# Sheet2.net
KiCad netlist of a schematic drawn in Altium Designer
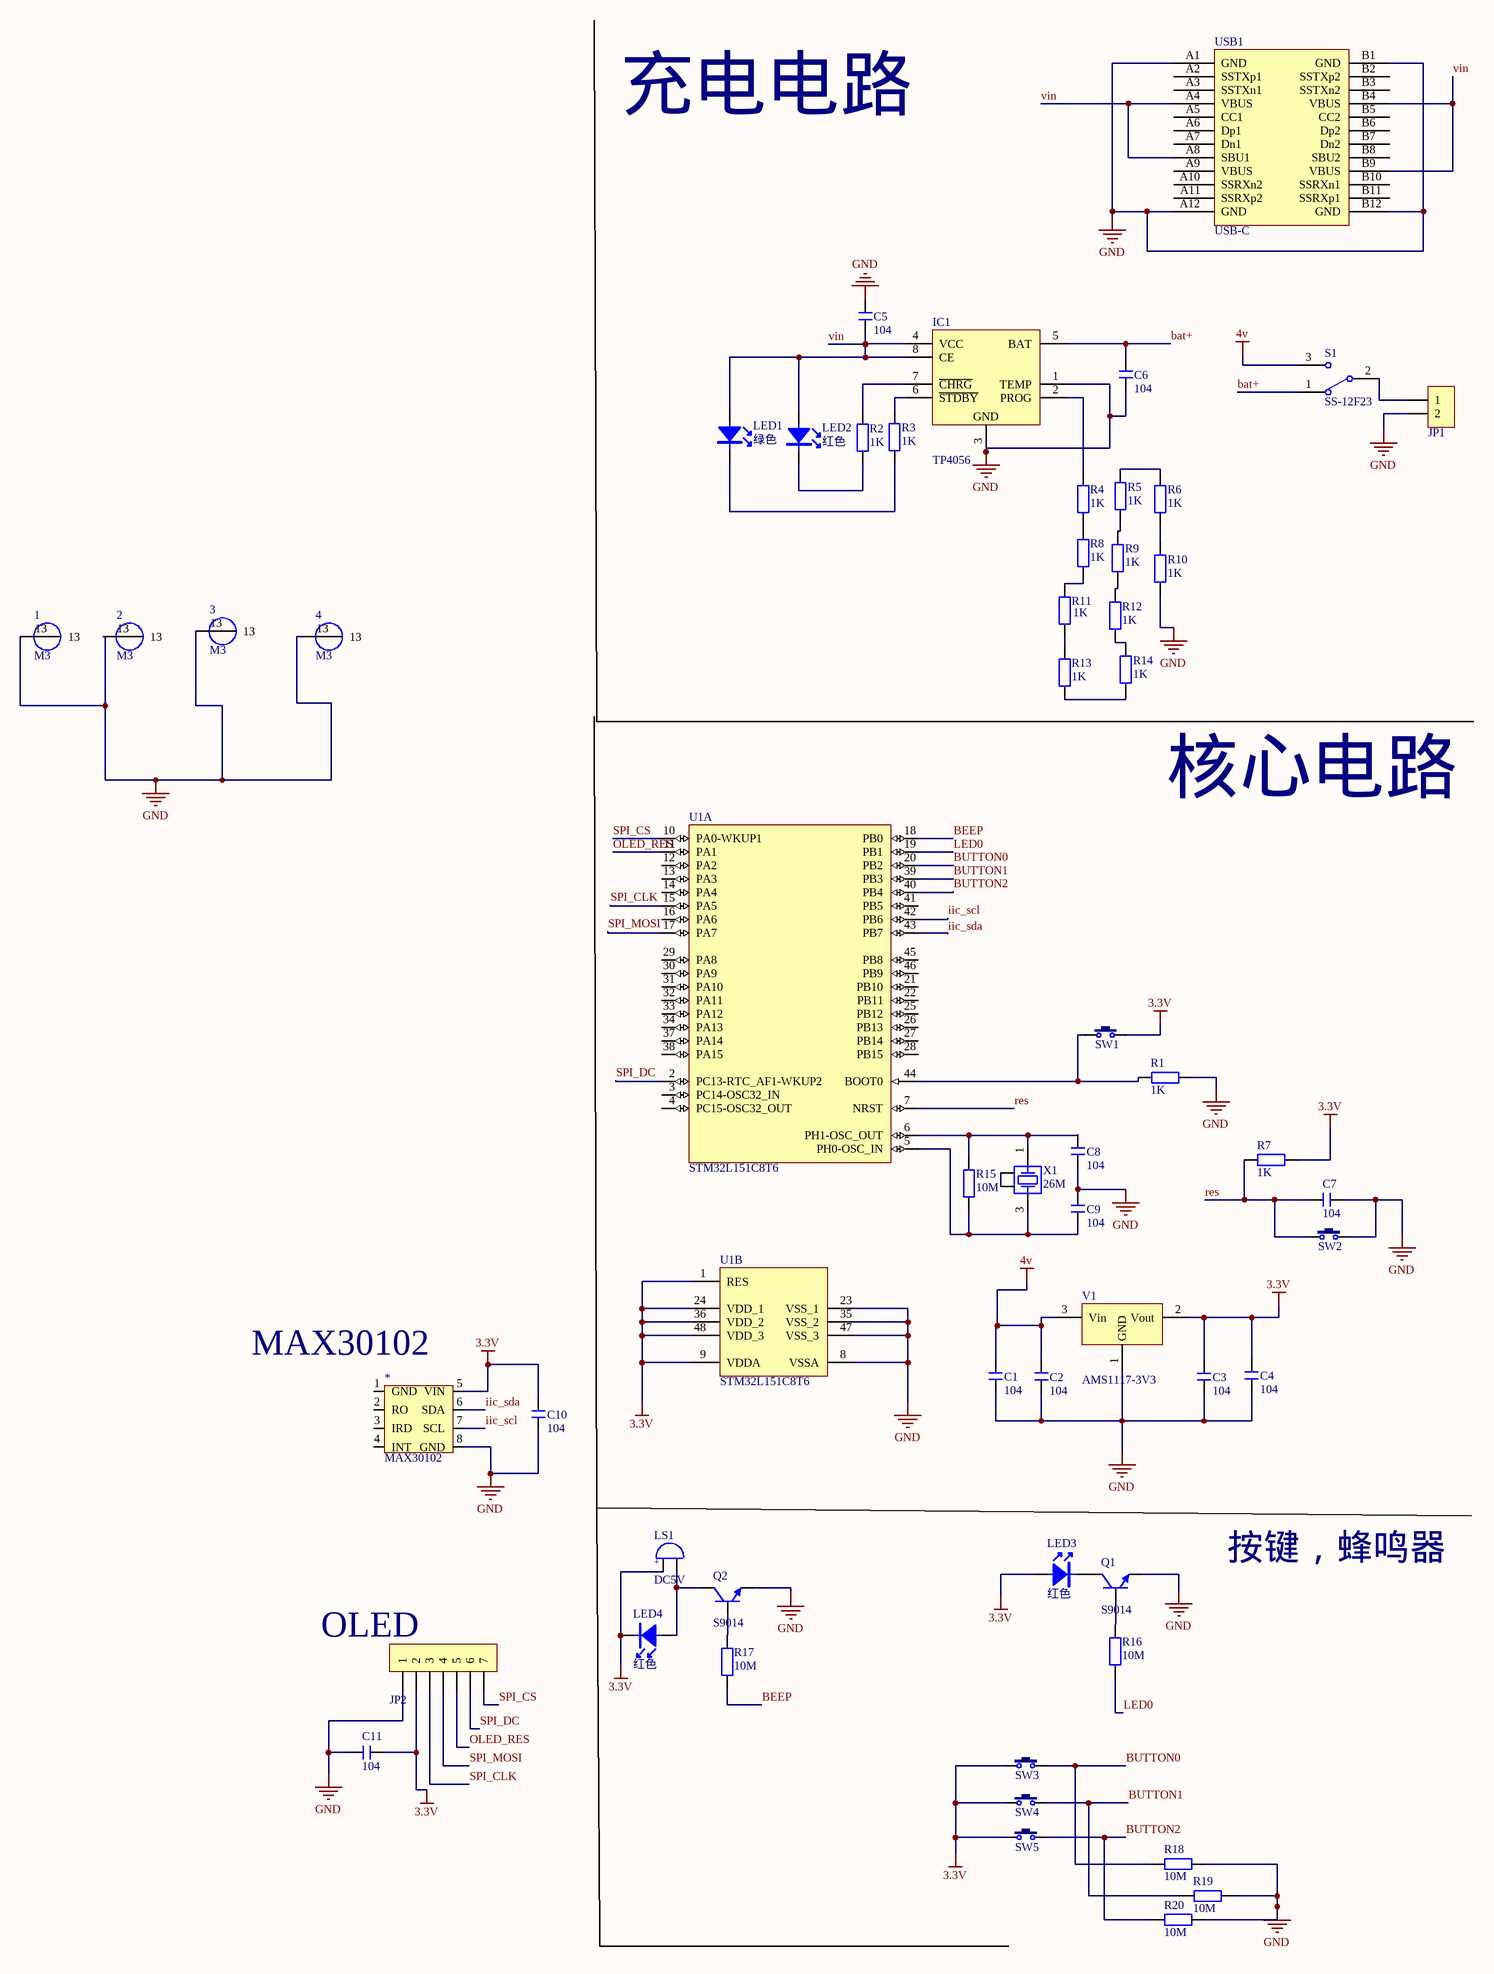
[diagram p0: Sheet2.SchDoc]

(export (version "E")
  (design (tool "Eeschema 10.0.6"))
  (components
    (comp (ref "*") (value "MAX30102") (footprint "MAX30102") (libsource (lib "Schlib1") (part "MAX30102")))
    (comp (ref "1")
      (value "M3")
      (footprint "M3 125X200")
      (description "铜柱孔")
      (libsource (lib "10 - 未分类元器件") (part "M3"))
    )
    (comp (ref "2")
      (value "M3")
      (footprint "M3 125X200")
      (description "铜柱孔")
      (libsource (lib "10 - 未分类元器件") (part "M3"))
    )
    (comp (ref "3")
      (value "M3")
      (footprint "M3 125X200")
      (description "铜柱孔")
      (libsource (lib "10 - 未分类元器件") (part "M3"))
    )
    (comp (ref "4")
      (value "M3")
      (footprint "M3 125X200")
      (description "铜柱孔")
      (libsource (lib "10 - 未分类元器件") (part "M3"))
    )
    (comp (ref "C1")
      (value "104")
      (footprint "C 0805_L")
      (description "贴片电容")
      (libsource (lib "01 - 电容-电阻-电感") (part "C"))
    )
    (comp (ref "C2")
      (value "104")
      (footprint "C 0805_L")
      (description "贴片电容")
      (libsource (lib "01 - 电容-电阻-电感") (part "C"))
    )
    (comp (ref "C3")
      (value "104")
      (footprint "C 0805_L")
      (description "贴片电容")
      (libsource (lib "01 - 电容-电阻-电感") (part "C"))
    )
    (comp (ref "C4")
      (value "104")
      (footprint "C 0805_L")
      (description "贴片电容")
      (libsource (lib "01 - 电容-电阻-电感") (part "C"))
    )
    (comp (ref "C5")
      (value "104")
      (footprint "C 0805_L")
      (description "贴片电容")
      (libsource (lib "01 - 电容-电阻-电感") (part "C"))
    )
    (comp (ref "C6")
      (value "104")
      (footprint "C 0805_L")
      (description "贴片电容")
      (libsource (lib "01 - 电容-电阻-电感") (part "C"))
    )
    (comp (ref "C7")
      (value "104")
      (footprint "C 0805_L")
      (description "贴片电容")
      (libsource (lib "01 - 电容-电阻-电感") (part "C"))
    )
    (comp (ref "C8")
      (value "104")
      (footprint "C 0805_L")
      (description "贴片电容")
      (libsource (lib "01 - 电容-电阻-电感") (part "C"))
    )
    (comp (ref "C9")
      (value "104")
      (footprint "C 0805_L")
      (description "贴片电容")
      (libsource (lib "01 - 电容-电阻-电感") (part "C"))
    )
    (comp (ref "C10")
      (value "104")
      (footprint "C 0805_L")
      (description "贴片电容")
      (libsource (lib "01 - 电容-电阻-电感") (part "C"))
    )
    (comp (ref "C11")
      (value "104")
      (footprint "C 0805_L")
      (description "贴片电容")
      (libsource (lib "01 - 电容-电阻-电感") (part "C"))
    )
    (comp (ref "IC1")
      (value "TP4056")
      (footprint "SOP8_N")
      (description "锂电池充电管理")
      (libsource (lib "08 - 稳压芯片-电源管理芯片") (part "TP4056"))
    )
    (comp (ref "JP1")
      (value "HDR-1X2")
      (footprint "HDR2.54-LI-2P")
      (description "2P接插件")
      (libsource (lib "16 - 接插件-脚距2.54mm (100mil) ") (part "Header 2"))
    )
    (comp (ref "JP2")
      (value "HDR-1X7")
      (footprint "HDR2.54-LI-7P")
      (description "7P接插件")
      (libsource (lib "16 - 接插件-脚距2.54mm (100mil) ") (part "Header 7"))
    )
    (comp (ref "LED1")
      (value "绿色")
      (footprint "LED 0805G")
      (description "贴片LED")
      (libsource (lib "02 - 二极管(LED)-三极管-整流桥") (part "LED-SMD"))
    )
    (comp (ref "LED2")
      (value "红色")
      (footprint "LED 0805G")
      (description "贴片LED")
      (libsource (lib "02 - 二极管(LED)-三极管-整流桥") (part "LED-SMD"))
    )
    (comp (ref "LED3")
      (value "红色")
      (footprint "LED 0805G")
      (description "贴片LED")
      (libsource (lib "02 - 二极管(LED)-三极管-整流桥") (part "LED-SMD"))
    )
    (comp (ref "LED4")
      (value "红色")
      (footprint "LED 0805G")
      (description "贴片LED")
      (libsource (lib "02 - 二极管(LED)-三极管-整流桥") (part "LED-SMD"))
    )
    (comp (ref "LS1")
      (value "DC5V")
      (footprint "BEEP 5x9x5.5")
      (description "有源蜂鸣器")
      (libsource (lib "03 - 按键-开关-晶振-蜂鸣器") (part "BEEP"))
    )
    (comp (ref "Q1")
      (value "S9014")
      (footprint "SOT23-3N")
      (description "低噪放大-NPN型")
      (libsource (lib "02 - 二极管(LED)-三极管-整流桥") (part "9014-SMD"))
    )
    (comp (ref "Q2")
      (value "S9014")
      (footprint "SOT23-3N")
      (description "低噪放大-NPN型")
      (libsource (lib "02 - 二极管(LED)-三极管-整流桥") (part "9014-SMD"))
    )
    (comp (ref "R1")
      (value "1K")
      (footprint "R 0805_L")
      (description "贴片电阻")
      (libsource (lib "01 - 电容-电阻-电感") (part "R"))
    )
    (comp (ref "R2")
      (value "1K")
      (footprint "R 0805_L")
      (description "贴片电阻")
      (libsource (lib "01 - 电容-电阻-电感") (part "R"))
    )
    (comp (ref "R3")
      (value "1K")
      (footprint "R 0805_L")
      (description "贴片电阻")
      (libsource (lib "01 - 电容-电阻-电感") (part "R"))
    )
    (comp (ref "R4")
      (value "1K")
      (footprint "R 0805_L")
      (description "贴片电阻")
      (libsource (lib "01 - 电容-电阻-电感") (part "R"))
    )
    (comp (ref "R5")
      (value "1K")
      (footprint "R 0805_L")
      (description "贴片电阻")
      (libsource (lib "01 - 电容-电阻-电感") (part "R"))
    )
    (comp (ref "R6")
      (value "1K")
      (footprint "R 0805_L")
      (description "贴片电阻")
      (libsource (lib "01 - 电容-电阻-电感") (part "R"))
    )
    (comp (ref "R7")
      (value "1K")
      (footprint "R 0805_L")
      (description "贴片电阻")
      (libsource (lib "01 - 电容-电阻-电感") (part "R"))
    )
    (comp (ref "R8")
      (value "1K")
      (footprint "R 0805_L")
      (description "贴片电阻")
      (libsource (lib "01 - 电容-电阻-电感") (part "R"))
    )
    (comp (ref "R9")
      (value "1K")
      (footprint "R 0805_L")
      (description "贴片电阻")
      (libsource (lib "01 - 电容-电阻-电感") (part "R"))
    )
    (comp (ref "R10")
      (value "1K")
      (footprint "R 0805_L")
      (description "贴片电阻")
      (libsource (lib "01 - 电容-电阻-电感") (part "R"))
    )
    (comp (ref "R11")
      (value "1K")
      (footprint "R 0805_L")
      (description "贴片电阻")
      (libsource (lib "01 - 电容-电阻-电感") (part "R"))
    )
    (comp (ref "R12")
      (value "1K")
      (footprint "R 0805_L")
      (description "贴片电阻")
      (libsource (lib "01 - 电容-电阻-电感") (part "R"))
    )
    (comp (ref "R13")
      (value "1K")
      (footprint "R 0805_L")
      (description "贴片电阻")
      (libsource (lib "01 - 电容-电阻-电感") (part "R"))
    )
    (comp (ref "R14")
      (value "1K")
      (footprint "R 0805_L")
      (description "贴片电阻")
      (libsource (lib "01 - 电容-电阻-电感") (part "R"))
    )
    (comp (ref "R15")
      (value "10M")
      (footprint "R 0805_L")
      (description "贴片电阻")
      (libsource (lib "01 - 电容-电阻-电感") (part "R"))
    )
    (comp (ref "R16")
      (value "10M")
      (footprint "R 0805_L")
      (description "贴片电阻")
      (libsource (lib "01 - 电容-电阻-电感") (part "R"))
    )
    (comp (ref "R17")
      (value "10M")
      (footprint "R 0805_L")
      (description "贴片电阻")
      (libsource (lib "01 - 电容-电阻-电感") (part "R"))
    )
    (comp (ref "R18")
      (value "10M")
      (footprint "R 0805_L")
      (description "贴片电阻")
      (libsource (lib "01 - 电容-电阻-电感") (part "R"))
    )
    (comp (ref "R19")
      (value "10M")
      (footprint "R 0805_L")
      (description "贴片电阻")
      (libsource (lib "01 - 电容-电阻-电感") (part "R"))
    )
    (comp (ref "R20")
      (value "10M")
      (footprint "R 0805_L")
      (description "贴片电阻")
      (libsource (lib "01 - 电容-电阻-电感") (part "R"))
    )
    (comp (ref "S1")
      (value "SS-12F23")
      (footprint "SS-12F23")
      (description "1路波动开关")
      (libsource (lib "03 - 按键-开关-晶振-蜂鸣器") (part "SSW-1P"))
    )
    (comp (ref "SW1")
      (value "3x6x5")
      (footprint "TSW SMD-3*6*2.5")
      (description "3x6轻触开关")
      (libsource (lib "03 - 按键-开关-晶振-蜂鸣器") (part "TSW 3x6"))
    )
    (comp (ref "SW2")
      (value "3x6x5")
      (footprint "TSW SMD-3*6*2.5")
      (description "3x6轻触开关")
      (libsource (lib "03 - 按键-开关-晶振-蜂鸣器") (part "TSW 3x6"))
    )
    (comp (ref "SW3")
      (value "3x6x5")
      (footprint "TSW SMD-3*6*2.5")
      (description "3x6轻触开关")
      (libsource (lib "03 - 按键-开关-晶振-蜂鸣器") (part "TSW 3x6"))
    )
    (comp (ref "SW4")
      (value "3x6x5")
      (footprint "TSW SMD-3*6*2.5")
      (description "3x6轻触开关")
      (libsource (lib "03 - 按键-开关-晶振-蜂鸣器") (part "TSW 3x6"))
    )
    (comp (ref "SW5")
      (value "3x6x5")
      (footprint "TSW SMD-3*6*2.5")
      (description "3x6轻触开关")
      (libsource (lib "03 - 按键-开关-晶振-蜂鸣器") (part "TSW 3x6"))
    )
    (comp (ref "U1")
      (value "STM32L151C8T6")
      (footprint "LQFP48_N")
      (libsource (lib "28 - STM32 L1系列单片机") (part "STM32L151C8T6"))
    )
    (comp (ref "USB1")
      (value "USB-C")
      (footprint "USB-C/S_A")
      (description "USB-C型母接口")
      (libsource (lib "04 - USB接口-网口-接口类") (part "USB-C/S"))
    )
    (comp (ref "V1")
      (value "AMS1117-3V3")
      (footprint "SOT223_L")
      (description "三端稳压芯片")
      (libsource (lib "08 - 稳压芯片-电源管理芯片") (part "AMS1117"))
    )
    (comp (ref "X1")
      (value "26M")
      (footprint "OSC 1612-4P")
      (description "4脚无源晶振")
      (libsource (lib "03 - 按键-开关-晶振-蜂鸣器") (part "XTAL-4P"))
    )
  )
  (nets
    (net (code "1") (name "/BEEP") (class "Default")
      (node (ref "R17") (pin "2") (pinfunction "2_2") (pintype "passive"))
      (node (ref "U1") (pin "18") (pinfunction "PB0_18") (pintype "bidirectional"))
    )
    (net (code "2") (name "/BUTTON0") (class "Default")
      (node (ref "R18") (pin "1") (pinfunction "1_1") (pintype "passive"))
      (node (ref "SW3") (pin "2") (pinfunction "2_2") (pintype "passive"))
      (node (ref "U1") (pin "20") (pinfunction "PB2_20") (pintype "bidirectional"))
    )
    (net (code "3") (name "/BUTTON1") (class "Default")
      (node (ref "R19") (pin "1") (pinfunction "1_1") (pintype "passive"))
      (node (ref "SW4") (pin "2") (pinfunction "2_2") (pintype "passive"))
      (node (ref "U1") (pin "39") (pinfunction "PB3_39") (pintype "bidirectional"))
    )
    (net (code "4") (name "/BUTTON2") (class "Default")
      (node (ref "R20") (pin "1") (pinfunction "1_1") (pintype "passive"))
      (node (ref "SW5") (pin "2") (pinfunction "2_2") (pintype "passive"))
      (node (ref "U1") (pin "40") (pinfunction "PB4_40") (pintype "bidirectional"))
    )
    (net (code "5") (name "/LED0") (class "Default")
      (node (ref "R16") (pin "2") (pinfunction "2_2") (pintype "passive"))
      (node (ref "U1") (pin "19") (pinfunction "PB1_19") (pintype "bidirectional"))
    )
    (net (code "6") (name "/OLED_RES") (class "Default")
      (node (ref "JP2") (pin "5") (pinfunction "5_5") (pintype "passive"))
      (node (ref "U1") (pin "11") (pinfunction "PA1_11") (pintype "bidirectional"))
    )
    (net (code "7") (name "/SPI_CLK") (class "Default")
      (node (ref "JP2") (pin "3") (pinfunction "3_3") (pintype "passive"))
      (node (ref "U1") (pin "15") (pinfunction "PA5_15") (pintype "bidirectional"))
    )
    (net (code "8") (name "/SPI_CS") (class "Default")
      (node (ref "JP2") (pin "7") (pinfunction "7_7") (pintype "passive"))
      (node (ref "U1") (pin "10") (pinfunction "PA0-WKUP1_10") (pintype "bidirectional"))
    )
    (net (code "9") (name "/SPI_DC") (class "Default")
      (node (ref "JP2") (pin "6") (pinfunction "6_6") (pintype "passive"))
      (node (ref "U1") (pin "2") (pinfunction "PC13-RTC_AF1-WKUP2_2") (pintype "bidirectional"))
    )
    (net (code "10") (name "/SPI_MOSI") (class "Default")
      (node (ref "JP2") (pin "4") (pinfunction "4_4") (pintype "passive"))
      (node (ref "U1") (pin "17") (pinfunction "PA7_17") (pintype "bidirectional"))
    )
    (net (code "11") (name "/bat+") (class "Default")
      (node (ref "C6") (pin "2") (pinfunction "2_2") (pintype "passive"))
      (node (ref "IC1") (pin "5") (pinfunction "BAT_5") (pintype "passive"))
      (node (ref "S1") (pin "1") (pinfunction "1_1") (pintype "passive"))
    )
    (net (code "12") (name "/iic_scl") (class "Default")
      (node (ref "*") (pin "7") (pinfunction "SCL_7") (pintype "passive"))
      (node (ref "U1") (pin "42") (pinfunction "PB6_42") (pintype "bidirectional"))
    )
    (net (code "13") (name "/iic_sda") (class "Default")
      (node (ref "*") (pin "6") (pinfunction "SDA_6") (pintype "passive"))
      (node (ref "U1") (pin "43") (pinfunction "PB7_43") (pintype "bidirectional"))
    )
    (net (code "14") (name "/res") (class "Default")
      (node (ref "C7") (pin "1") (pinfunction "1_1") (pintype "passive"))
      (node (ref "R7") (pin "2") (pinfunction "2_2") (pintype "passive"))
      (node (ref "SW2") (pin "1") (pinfunction "1_1") (pintype "passive"))
      (node (ref "U1") (pin "7") (pinfunction "NRST_7") (pintype "bidirectional"))
    )
    (net (code "15") (name "/vin") (class "Default")
      (node (ref "C5") (pin "1") (pinfunction "1_1") (pintype "passive"))
      (node (ref "IC1") (pin "4") (pinfunction "VCC_4") (pintype "passive"))
      (node (ref "IC1") (pin "8") (pinfunction "CE_8") (pintype "passive"))
      (node (ref "LED1") (pin "1") (pinfunction "A_1") (pintype "passive"))
      (node (ref "LED2") (pin "1") (pinfunction "A_1") (pintype "passive"))
      (node (ref "USB1") (pin "A4") (pinfunction "VBUS_A4") (pintype "passive"))
      (node (ref "USB1") (pin "A8") (pinfunction "SBU1_A8") (pintype "passive"))
      (node (ref "USB1") (pin "B4") (pinfunction "VBUS_B4") (pintype "passive"))
      (node (ref "USB1") (pin "B9") (pinfunction "VBUS_B9") (pintype "passive"))
    )
    (net (code "16") (name "3.3V") (class "Default")
      (node (ref "*") (pin "5") (pinfunction "VIN_5") (pintype "passive"))
      (node (ref "C10") (pin "1") (pinfunction "1_1") (pintype "passive"))
      (node (ref "C11") (pin "1") (pinfunction "1_1") (pintype "passive"))
      (node (ref "C3") (pin "1") (pinfunction "1_1") (pintype "passive"))
      (node (ref "C4") (pin "1") (pinfunction "1_1") (pintype "passive"))
      (node (ref "JP2") (pin "2") (pinfunction "2_2") (pintype "passive"))
      (node (ref "LED3") (pin "1") (pinfunction "A_1") (pintype "passive"))
      (node (ref "LED4") (pin "2") (pinfunction "K_2") (pintype "passive"))
      (node (ref "LS1") (pin "1") (pinfunction "1_1") (pintype "passive"))
      (node (ref "R7") (pin "1") (pinfunction "1_1") (pintype "passive"))
      (node (ref "SW1") (pin "2") (pinfunction "2_2") (pintype "passive"))
      (node (ref "SW3") (pin "1") (pinfunction "1_1") (pintype "passive"))
      (node (ref "SW4") (pin "1") (pinfunction "1_1") (pintype "passive"))
      (node (ref "SW5") (pin "1") (pinfunction "1_1") (pintype "passive"))
      (node (ref "U1") (pin "1") (pinfunction "RES_1") (pintype "power_in"))
      (node (ref "U1") (pin "24") (pinfunction "VDD_1_24") (pintype "power_in"))
      (node (ref "U1") (pin "36") (pinfunction "VDD_2_36") (pintype "power_in"))
      (node (ref "U1") (pin "48") (pinfunction "VDD_3_48") (pintype "power_in"))
      (node (ref "U1") (pin "9") (pinfunction "VDDA_9") (pintype "power_in"))
      (node (ref "V1") (pin "2") (pinfunction "Vout_2") (pintype "passive"))
    )
    (net (code "17") (name "4v") (class "Default")
      (node (ref "C1") (pin "1") (pinfunction "1_1") (pintype "passive"))
      (node (ref "C2") (pin "1") (pinfunction "1_1") (pintype "passive"))
      (node (ref "S1") (pin "3") (pinfunction "3_3") (pintype "passive"))
      (node (ref "V1") (pin "3") (pinfunction "Vin_3") (pintype "passive"))
    )
    (net (code "18") (name "GND") (class "Default")
      (node (ref "*") (pin "8") (pinfunction "GND_8") (pintype "passive"))
      (node (ref "1") (pin "13") (pinfunction "13_13") (pintype "passive"))
      (node (ref "2") (pin "13") (pinfunction "13_13") (pintype "passive"))
      (node (ref "3") (pin "13") (pinfunction "13_13") (pintype "passive"))
      (node (ref "4") (pin "13") (pinfunction "13_13") (pintype "passive"))
      (node (ref "C1") (pin "2") (pinfunction "2_2") (pintype "passive"))
      (node (ref "C10") (pin "2") (pinfunction "2_2") (pintype "passive"))
      (node (ref "C11") (pin "2") (pinfunction "2_2") (pintype "passive"))
      (node (ref "C2") (pin "2") (pinfunction "2_2") (pintype "passive"))
      (node (ref "C3") (pin "2") (pinfunction "2_2") (pintype "passive"))
      (node (ref "C4") (pin "2") (pinfunction "2_2") (pintype "passive"))
      (node (ref "C5") (pin "2") (pinfunction "2_2") (pintype "passive"))
      (node (ref "C6") (pin "1") (pinfunction "1_1") (pintype "passive"))
      (node (ref "C7") (pin "2") (pinfunction "2_2") (pintype "passive"))
      (node (ref "C8") (pin "2") (pinfunction "2_2") (pintype "passive"))
      (node (ref "C9") (pin "1") (pinfunction "1_1") (pintype "passive"))
      (node (ref "IC1") (pin "1") (pinfunction "TEMP_1") (pintype "passive"))
      (node (ref "IC1") (pin "3") (pinfunction "GND_3") (pintype "passive"))
      (node (ref "JP1") (pin "2") (pinfunction "2_2") (pintype "passive"))
      (node (ref "JP2") (pin "1") (pinfunction "1_1") (pintype "passive"))
      (node (ref "Q1") (pin "2") (pinfunction "E_2") (pintype "passive"))
      (node (ref "Q2") (pin "2") (pinfunction "E_2") (pintype "passive"))
      (node (ref "R1") (pin "1") (pinfunction "1_1") (pintype "passive"))
      (node (ref "R10") (pin "2") (pinfunction "2_2") (pintype "passive"))
      (node (ref "R18") (pin "2") (pinfunction "2_2") (pintype "passive"))
      (node (ref "R19") (pin "2") (pinfunction "2_2") (pintype "passive"))
      (node (ref "R20") (pin "2") (pinfunction "2_2") (pintype "passive"))
      (node (ref "SW2") (pin "2") (pinfunction "2_2") (pintype "passive"))
      (node (ref "U1") (pin "23") (pinfunction "VSS_1_23") (pintype "power_in"))
      (node (ref "U1") (pin "35") (pinfunction "VSS_2_35") (pintype "power_in"))
      (node (ref "U1") (pin "47") (pinfunction "VSS_3_47") (pintype "power_in"))
      (node (ref "U1") (pin "8") (pinfunction "VSSA_8") (pintype "power_in"))
      (node (ref "USB1") (pin "A1") (pinfunction "GND_A1") (pintype "passive"))
      (node (ref "USB1") (pin "A12") (pinfunction "GND_A12") (pintype "passive"))
      (node (ref "USB1") (pin "B1") (pinfunction "GND_B1") (pintype "passive"))
      (node (ref "USB1") (pin "B12") (pinfunction "GND_B12") (pintype "passive"))
      (node (ref "V1") (pin "1") (pinfunction "GND_1") (pintype "passive"))
    )
    (net (code "19") (name "Net-(IC1-PROG)") (class "Default")
      (node (ref "IC1") (pin "2") (pinfunction "PROG_2") (pintype "passive"))
      (node (ref "R4") (pin "1") (pinfunction "1_1") (pintype "passive"))
    )
    (net (code "20") (name "Net-(IC1-~{CHRG})") (class "Default")
      (node (ref "IC1") (pin "7") (pinfunction "~{CHRG}_7") (pintype "passive"))
      (node (ref "R2") (pin "1") (pinfunction "1_1") (pintype "passive"))
    )
    (net (code "21") (name "Net-(IC1-~{STDBY})") (class "Default")
      (node (ref "IC1") (pin "6") (pinfunction "~{STDBY}_6") (pintype "passive"))
      (node (ref "R3") (pin "1") (pinfunction "1_1") (pintype "passive"))
    )
    (net (code "22") (name "Net-(JP1-Pad1)") (class "Default")
      (node (ref "JP1") (pin "1") (pinfunction "1_1") (pintype "passive"))
      (node (ref "S1") (pin "2") (pinfunction "2_2") (pintype "passive"))
    )
    (net (code "23") (name "Net-(LED1-K)") (class "Default")
      (node (ref "LED1") (pin "2") (pinfunction "K_2") (pintype "passive"))
      (node (ref "R3") (pin "2") (pinfunction "2_2") (pintype "passive"))
    )
    (net (code "24") (name "Net-(LED2-K)") (class "Default")
      (node (ref "LED2") (pin "2") (pinfunction "K_2") (pintype "passive"))
      (node (ref "R2") (pin "2") (pinfunction "2_2") (pintype "passive"))
    )
    (net (code "25") (name "Net-(LED3-K)") (class "Default")
      (node (ref "LED3") (pin "2") (pinfunction "K_2") (pintype "passive"))
      (node (ref "Q1") (pin "3") (pinfunction "C_3") (pintype "passive"))
    )
    (net (code "26") (name "Net-(LED4-A)") (class "Default")
      (node (ref "LED4") (pin "1") (pinfunction "A_1") (pintype "passive"))
      (node (ref "LS1") (pin "2") (pinfunction "2_2") (pintype "passive"))
      (node (ref "Q2") (pin "3") (pinfunction "C_3") (pintype "passive"))
    )
    (net (code "27") (name "Net-(Q1-B)") (class "Default")
      (node (ref "Q1") (pin "1") (pinfunction "B_1") (pintype "passive"))
      (node (ref "R16") (pin "1") (pinfunction "1_1") (pintype "passive"))
    )
    (net (code "28") (name "Net-(Q2-B)") (class "Default")
      (node (ref "Q2") (pin "1") (pinfunction "B_1") (pintype "passive"))
      (node (ref "R17") (pin "1") (pinfunction "1_1") (pintype "passive"))
    )
    (net (code "29") (name "Net-(R4-Pad2)") (class "Default")
      (node (ref "R4") (pin "2") (pinfunction "2_2") (pintype "passive"))
      (node (ref "R8") (pin "1") (pinfunction "1_1") (pintype "passive"))
    )
    (net (code "30") (name "Net-(R5-Pad1)") (class "Default")
      (node (ref "R5") (pin "1") (pinfunction "1_1") (pintype "passive"))
      (node (ref "R6") (pin "1") (pinfunction "1_1") (pintype "passive"))
    )
    (net (code "31") (name "Net-(R5-Pad2)") (class "Default")
      (node (ref "R5") (pin "2") (pinfunction "2_2") (pintype "passive"))
      (node (ref "R9") (pin "1") (pinfunction "1_1") (pintype "passive"))
    )
    (net (code "32") (name "Net-(R10-Pad1)") (class "Default")
      (node (ref "R10") (pin "1") (pinfunction "1_1") (pintype "passive"))
      (node (ref "R6") (pin "2") (pinfunction "2_2") (pintype "passive"))
    )
    (net (code "33") (name "Net-(R11-Pad1)") (class "Default")
      (node (ref "R11") (pin "1") (pinfunction "1_1") (pintype "passive"))
      (node (ref "R8") (pin "2") (pinfunction "2_2") (pintype "passive"))
    )
    (net (code "34") (name "Net-(R11-Pad2)") (class "Default")
      (node (ref "R11") (pin "2") (pinfunction "2_2") (pintype "passive"))
      (node (ref "R13") (pin "1") (pinfunction "1_1") (pintype "passive"))
    )
    (net (code "35") (name "Net-(R12-Pad1)") (class "Default")
      (node (ref "R12") (pin "1") (pinfunction "1_1") (pintype "passive"))
      (node (ref "R9") (pin "2") (pinfunction "2_2") (pintype "passive"))
    )
    (net (code "36") (name "Net-(R12-Pad2)") (class "Default")
      (node (ref "R12") (pin "2") (pinfunction "2_2") (pintype "passive"))
      (node (ref "R14") (pin "1") (pinfunction "1_1") (pintype "passive"))
    )
    (net (code "37") (name "Net-(R13-Pad2)") (class "Default")
      (node (ref "R13") (pin "2") (pinfunction "2_2") (pintype "passive"))
      (node (ref "R14") (pin "2") (pinfunction "2_2") (pintype "passive"))
    )
    (net (code "38") (name "Net-(U1A-BOOT0)") (class "Default")
      (node (ref "R1") (pin "2") (pinfunction "2_2") (pintype "passive"))
      (node (ref "SW1") (pin "1") (pinfunction "1_1") (pintype "passive"))
      (node (ref "U1") (pin "44") (pinfunction "BOOT0_44") (pintype "input"))
    )
    (net (code "39") (name "Net-(U1A-PH0-OSC_IN)") (class "Default")
      (node (ref "C9") (pin "2") (pinfunction "2_2") (pintype "passive"))
      (node (ref "R15") (pin "2") (pinfunction "2_2") (pintype "passive"))
      (node (ref "U1") (pin "5") (pinfunction "PH0-OSC_IN_5") (pintype "bidirectional"))
      (node (ref "X1") (pin "3") (pinfunction "3_3") (pintype "passive"))
    )
    (net (code "40") (name "Net-(U1A-PH1-OSC_OUT)") (class "Default")
      (node (ref "C8") (pin "1") (pinfunction "1_1") (pintype "passive"))
      (node (ref "R15") (pin "1") (pinfunction "1_1") (pintype "passive"))
      (node (ref "U1") (pin "6") (pinfunction "PH1-OSC_OUT_6") (pintype "bidirectional"))
      (node (ref "X1") (pin "1") (pinfunction "1_1") (pintype "passive"))
    )
    (net (code "41") (name "Net-(X1-Pad2)") (class "Default")
      (node (ref "X1") (pin "2") (pinfunction "2_2") (pintype "passive"))
      (node (ref "X1") (pin "4") (pinfunction "4_4") (pintype "passive"))
    )
    (net (code "42") (name "unconnected-(*-GND-Pad1)") (class "Default")
      (node (ref "*") (pin "1") (pinfunction "GND_1") (pintype "passive"))
    )
    (net (code "43") (name "unconnected-(*-INT-Pad4)") (class "Default")
      (node (ref "*") (pin "4") (pinfunction "INT_4") (pintype "passive"))
    )
    (net (code "44") (name "unconnected-(*-IRD-Pad3)") (class "Default")
      (node (ref "*") (pin "3") (pinfunction "IRD_3") (pintype "passive"))
    )
    (net (code "45") (name "unconnected-(*-RO-Pad2)") (class "Default")
      (node (ref "*") (pin "2") (pinfunction "RO_2") (pintype "passive"))
    )
    (net (code "46") (name "unconnected-(U1A-PA2-Pad12)") (class "Default")
      (node (ref "U1") (pin "12") (pinfunction "PA2_12") (pintype "bidirectional"))
    )
    (net (code "47") (name "unconnected-(U1A-PA3-Pad13)") (class "Default")
      (node (ref "U1") (pin "13") (pinfunction "PA3_13") (pintype "bidirectional"))
    )
    (net (code "48") (name "unconnected-(U1A-PA4-Pad14)") (class "Default")
      (node (ref "U1") (pin "14") (pinfunction "PA4_14") (pintype "bidirectional"))
    )
    (net (code "49") (name "unconnected-(U1A-PA6-Pad16)") (class "Default")
      (node (ref "U1") (pin "16") (pinfunction "PA6_16") (pintype "bidirectional"))
    )
    (net (code "50") (name "unconnected-(U1A-PA8-Pad29)") (class "Default")
      (node (ref "U1") (pin "29") (pinfunction "PA8_29") (pintype "bidirectional"))
    )
    (net (code "51") (name "unconnected-(U1A-PA9-Pad30)") (class "Default")
      (node (ref "U1") (pin "30") (pinfunction "PA9_30") (pintype "bidirectional"))
    )
    (net (code "52") (name "unconnected-(U1A-PA10-Pad31)") (class "Default")
      (node (ref "U1") (pin "31") (pinfunction "PA10_31") (pintype "bidirectional"))
    )
    (net (code "53") (name "unconnected-(U1A-PA11-Pad32)") (class "Default")
      (node (ref "U1") (pin "32") (pinfunction "PA11_32") (pintype "bidirectional"))
    )
    (net (code "54") (name "unconnected-(U1A-PA12-Pad33)") (class "Default")
      (node (ref "U1") (pin "33") (pinfunction "PA12_33") (pintype "bidirectional"))
    )
    (net (code "55") (name "unconnected-(U1A-PA13-Pad34)") (class "Default")
      (node (ref "U1") (pin "34") (pinfunction "PA13_34") (pintype "bidirectional"))
    )
    (net (code "56") (name "unconnected-(U1A-PA14-Pad37)") (class "Default")
      (node (ref "U1") (pin "37") (pinfunction "PA14_37") (pintype "bidirectional"))
    )
    (net (code "57") (name "unconnected-(U1A-PA15-Pad38)") (class "Default")
      (node (ref "U1") (pin "38") (pinfunction "PA15_38") (pintype "bidirectional"))
    )
    (net (code "58") (name "unconnected-(U1A-PB5-Pad41)") (class "Default")
      (node (ref "U1") (pin "41") (pinfunction "PB5_41") (pintype "bidirectional"))
    )
    (net (code "59") (name "unconnected-(U1A-PB8-Pad45)") (class "Default")
      (node (ref "U1") (pin "45") (pinfunction "PB8_45") (pintype "bidirectional"))
    )
    (net (code "60") (name "unconnected-(U1A-PB9-Pad46)") (class "Default")
      (node (ref "U1") (pin "46") (pinfunction "PB9_46") (pintype "bidirectional"))
    )
    (net (code "61") (name "unconnected-(U1A-PB10-Pad21)") (class "Default")
      (node (ref "U1") (pin "21") (pinfunction "PB10_21") (pintype "bidirectional"))
    )
    (net (code "62") (name "unconnected-(U1A-PB11-Pad22)") (class "Default")
      (node (ref "U1") (pin "22") (pinfunction "PB11_22") (pintype "bidirectional"))
    )
    (net (code "63") (name "unconnected-(U1A-PB12-Pad25)") (class "Default")
      (node (ref "U1") (pin "25") (pinfunction "PB12_25") (pintype "bidirectional"))
    )
    (net (code "64") (name "unconnected-(U1A-PB13-Pad26)") (class "Default")
      (node (ref "U1") (pin "26") (pinfunction "PB13_26") (pintype "bidirectional"))
    )
    (net (code "65") (name "unconnected-(U1A-PB14-Pad27)") (class "Default")
      (node (ref "U1") (pin "27") (pinfunction "PB14_27") (pintype "bidirectional"))
    )
    (net (code "66") (name "unconnected-(U1A-PB15-Pad28)") (class "Default")
      (node (ref "U1") (pin "28") (pinfunction "PB15_28") (pintype "bidirectional"))
    )
    (net (code "67") (name "unconnected-(U1A-PC14-OSC32_IN-Pad3)") (class "Default")
      (node (ref "U1") (pin "3") (pinfunction "PC14-OSC32_IN_3") (pintype "bidirectional"))
    )
    (net (code "68") (name "unconnected-(U1A-PC15-OSC32_OUT-Pad4)") (class "Default")
      (node (ref "U1") (pin "4") (pinfunction "PC15-OSC32_OUT_4") (pintype "bidirectional"))
    )
    (net (code "69") (name "unconnected-(USB1-CC1-PadA5)") (class "Default")
      (node (ref "USB1") (pin "A5") (pinfunction "CC1_A5") (pintype "passive"))
    )
    (net (code "70") (name "unconnected-(USB1-CC2-PadB5)") (class "Default")
      (node (ref "USB1") (pin "B5") (pinfunction "CC2_B5") (pintype "passive"))
    )
    (net (code "71") (name "unconnected-(USB1-Dn1-PadA7)") (class "Default")
      (node (ref "USB1") (pin "A7") (pinfunction "Dn1_A7") (pintype "passive"))
    )
    (net (code "72") (name "unconnected-(USB1-Dn2-PadB7)") (class "Default")
      (node (ref "USB1") (pin "B7") (pinfunction "Dn2_B7") (pintype "passive"))
    )
    (net (code "73") (name "unconnected-(USB1-Dp1-PadA6)") (class "Default")
      (node (ref "USB1") (pin "A6") (pinfunction "Dp1_A6") (pintype "passive"))
    )
    (net (code "74") (name "unconnected-(USB1-Dp2-PadB6)") (class "Default")
      (node (ref "USB1") (pin "B6") (pinfunction "Dp2_B6") (pintype "passive"))
    )
    (net (code "75") (name "unconnected-(USB1-SBU2-PadB8)") (class "Default")
      (node (ref "USB1") (pin "B8") (pinfunction "SBU2_B8") (pintype "passive"))
    )
    (net (code "76") (name "unconnected-(USB1-SSRXn1-PadB10)") (class "Default")
      (node (ref "USB1") (pin "B10") (pinfunction "SSRXn1_B10") (pintype "passive"))
    )
    (net (code "77") (name "unconnected-(USB1-SSRXn2-PadA10)") (class "Default")
      (node (ref "USB1") (pin "A10") (pinfunction "SSRXn2_A10") (pintype "passive"))
    )
    (net (code "78") (name "unconnected-(USB1-SSRXp1-PadB11)") (class "Default")
      (node (ref "USB1") (pin "B11") (pinfunction "SSRXp1_B11") (pintype "passive"))
    )
    (net (code "79") (name "unconnected-(USB1-SSRXp2-PadA11)") (class "Default")
      (node (ref "USB1") (pin "A11") (pinfunction "SSRXp2_A11") (pintype "passive"))
    )
    (net (code "80") (name "unconnected-(USB1-SSTXn1-PadA3)") (class "Default")
      (node (ref "USB1") (pin "A3") (pinfunction "SSTXn1_A3") (pintype "passive"))
    )
    (net (code "81") (name "unconnected-(USB1-SSTXn2-PadB3)") (class "Default")
      (node (ref "USB1") (pin "B3") (pinfunction "SSTXn2_B3") (pintype "passive"))
    )
    (net (code "82") (name "unconnected-(USB1-SSTXp1-PadA2)") (class "Default")
      (node (ref "USB1") (pin "A2") (pinfunction "SSTXp1_A2") (pintype "passive"))
    )
    (net (code "83") (name "unconnected-(USB1-SSTXp2-PadB2)") (class "Default")
      (node (ref "USB1") (pin "B2") (pinfunction "SSTXp2_B2") (pintype "passive"))
    )
    (net (code "84") (name "unconnected-(USB1-VBUS-PadA9)") (class "Default")
      (node (ref "USB1") (pin "A9") (pinfunction "VBUS_A9") (pintype "passive"))
    )
  )
)
